# Ethernet-HPS.net
KiCad netlist of a schematic drawn in Altium Designer
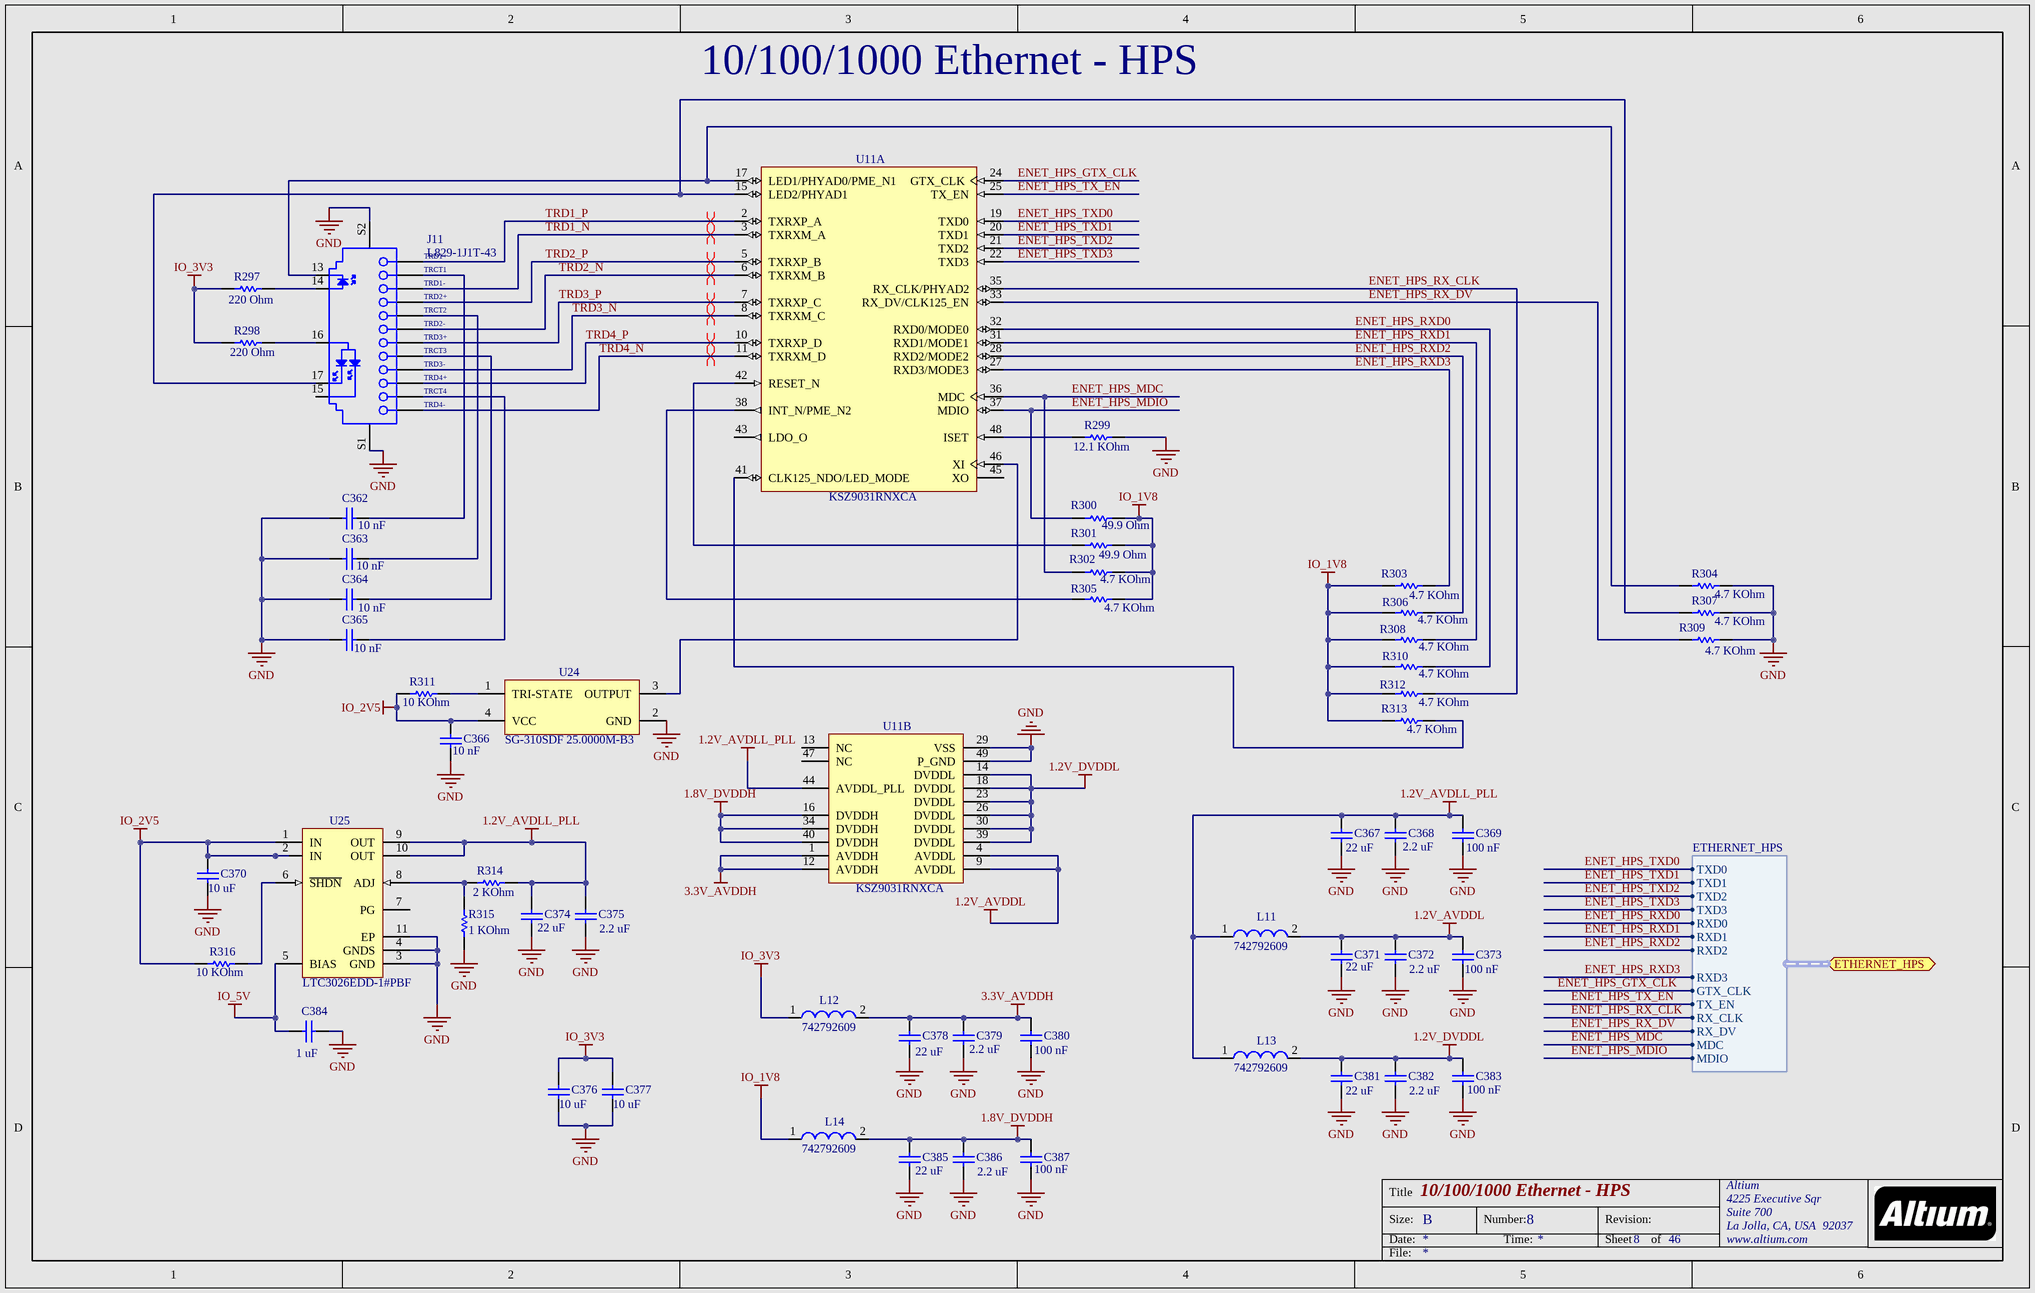
[diagram p0: Ethernet-HPS.SchDoc]

(export (version "E")
  (design (tool "Eeschema 10.0.6"))
  (components
    (comp (ref "C362")
      (value "GRM155R71H103KA88D")
      (footprint "CAPC1005X55X25ML05T10")
      (description "Chip Capacitor, 10 nF, +/- 10%, 50 V, -55 to 125 degC, 0402 (1005 Metric), RoHS, Tape and Reel")
      (fields
        (field (name "TOLERANCE") "10%")
        (field (name "CAPACITANCE") "10 nF")
        (field (name "MANUFACTURER") "Basic Passives")
      )
      (libsource (lib "") (part "CAP-NP-2_1"))
    )
    (comp (ref "C363")
      (value "GRM155R71H103KA88D")
      (footprint "CAPC1005X55X25ML05T10")
      (description "Chip Capacitor, 10 nF, +/- 10%, 50 V, -55 to 125 degC, 0402 (1005 Metric), RoHS, Tape and Reel")
      (fields
        (field (name "TOLERANCE") "10%")
        (field (name "CAPACITANCE") "10 nF")
        (field (name "MANUFACTURER") "Basic Passives")
      )
      (libsource (lib "") (part "CAP-NP-2_1"))
    )
    (comp (ref "C364")
      (value "GRM155R71H103KA88D")
      (footprint "CAPC1005X55X25ML05T10")
      (description "Chip Capacitor, 10 nF, +/- 10%, 50 V, -55 to 125 degC, 0402 (1005 Metric), RoHS, Tape and Reel")
      (fields
        (field (name "TOLERANCE") "10%")
        (field (name "CAPACITANCE") "10 nF")
        (field (name "MANUFACTURER") "Basic Passives")
      )
      (libsource (lib "") (part "CAP-NP-2_1"))
    )
    (comp (ref "C365")
      (value "GRM155R71H103KA88D")
      (footprint "CAPC1005X55X25ML05T10")
      (description "Chip Capacitor, 10 nF, +/- 10%, 50 V, -55 to 125 degC, 0402 (1005 Metric), RoHS, Tape and Reel")
      (fields
        (field (name "TOLERANCE") "10%")
        (field (name "CAPACITANCE") "10 nF")
        (field (name "MANUFACTURER") "Basic Passives")
      )
      (libsource (lib "") (part "CAP-NP-2_1"))
    )
    (comp (ref "C366")
      (value "GRM155R71H103KA88D")
      (footprint "CAPC1005X55X25ML05T10")
      (description "Chip Capacitor, 10 nF, +/- 10%, 50 V, -55 to 125 degC, 0402 (1005 Metric), RoHS, Tape and Reel")
      (fields
        (field (name "TOLERANCE") "10%")
        (field (name "CAPACITANCE") "10 nF")
        (field (name "MANUFACTURER") "Basic Passives")
      )
      (libsource (lib "") (part "CAP-NP-2_1"))
    )
    (comp (ref "C367")
      (value "GRM31CR61E226KE15L")
      (footprint "CAPC3216X180X55ML20T25")
      (description "Chip Capacitor, 22 uF, +/- 10%, 25 V, -55 to 85 degC, 1206 (3216 Metric), RoHS, Tape and Reel")
      (fields (field (name "TOLERANCE") "10%") (field (name "CAPACITANCE") "22 uF"))
      (libsource (lib "") (part "CAP-NP-2_1"))
    )
    (comp (ref "C368")
      (value "GRM188R61A225KE34x")
      (footprint "CAPC1608X90X35ML10T15")
      (description "Chip Capacitor, 2.2 uF, +/- 10%, 10 V, -55 to 85 degC, 0603 (1608 Metric), RoHS, Tape and Reel")
      (fields (field (name "TOLERANCE") "10%") (field (name "CAPACITANCE") "2.2 uF"))
      (libsource (lib "Altium Content Vault") (part "CAP-NP-2"))
    )
    (comp (ref "C369")
      (value "C1005X7R1E104M")
      (footprint "CAPC1005X55X10LL05")
      (description "Chip Capacitor, 0.1 uF, +/- 20%, 25 V, -55 to 125 degC, 0402 (1005 Metric), RoHS, Tape and Reel")
      (fields (field (name "TOLERANCE") "20%") (field (name "CAPACITANCE") "100 nF"))
      (libsource (lib "") (part "CAP-NP-2_1"))
    )
    (comp (ref "C370")
      (value "C2012X5R1C106K085AC")
      (footprint "CAPC2013X100X20NL20")
      (description "Chip Capacitor, 10 uF, +/- 10%, 16 V, -55 to 85 degC, 0805 (2012 Metric), RoHS, Tape and Reel")
      (fields (field (name "TOLERANCE") "10%") (field (name "CAPACITANCE") "10 uF"))
      (libsource (lib "Altium Content Vault") (part "CAP-NP-2"))
    )
    (comp (ref "C371")
      (value "GRM31CR61E226KE15L")
      (footprint "CAPC3216X180X55ML20T25")
      (description "Chip Capacitor, 22 uF, +/- 10%, 25 V, -55 to 85 degC, 1206 (3216 Metric), RoHS, Tape and Reel")
      (fields (field (name "TOLERANCE") "10%") (field (name "CAPACITANCE") "22 uF"))
      (libsource (lib "") (part "CAP-NP-2_1"))
    )
    (comp (ref "C372")
      (value "GRM188R61A225KE34x")
      (footprint "CAPC1608X90X35ML10T15")
      (description "Chip Capacitor, 2.2 uF, +/- 10%, 10 V, -55 to 85 degC, 0603 (1608 Metric), RoHS, Tape and Reel")
      (fields (field (name "TOLERANCE") "10%") (field (name "CAPACITANCE") "2.2 uF"))
      (libsource (lib "Altium Content Vault") (part "CAP-NP-2"))
    )
    (comp (ref "C373")
      (value "C1005X7R1E104M")
      (footprint "CAPC1005X55X10LL05")
      (description "Chip Capacitor, 0.1 uF, +/- 20%, 25 V, -55 to 125 degC, 0402 (1005 Metric), RoHS, Tape and Reel")
      (fields (field (name "TOLERANCE") "20%") (field (name "CAPACITANCE") "100 nF"))
      (libsource (lib "") (part "CAP-NP-2_1"))
    )
    (comp (ref "C374")
      (value "GRM31CR61E226KE15L")
      (footprint "CAPC3216X180X55ML20T25")
      (description "Chip Capacitor, 22 uF, +/- 10%, 25 V, -55 to 85 degC, 1206 (3216 Metric), RoHS, Tape and Reel")
      (fields (field (name "TOLERANCE") "10%") (field (name "CAPACITANCE") "22 uF"))
      (libsource (lib "") (part "CAP-NP-2_1"))
    )
    (comp (ref "C375")
      (value "GRM188R61A225KE34x")
      (footprint "CAPC1608X90X35ML10T15")
      (description "Chip Capacitor, 2.2 uF, +/- 10%, 10 V, -55 to 85 degC, 0603 (1608 Metric), RoHS, Tape and Reel")
      (fields (field (name "TOLERANCE") "10%") (field (name "CAPACITANCE") "2.2 uF"))
      (libsource (lib "Altium Content Vault") (part "CAP-NP-2"))
    )
    (comp (ref "C376")
      (value "C2012X5R1C106K085AC")
      (footprint "CAPC2013X100X20NL20")
      (description "Chip Capacitor, 10 uF, +/- 10%, 16 V, -55 to 85 degC, 0805 (2012 Metric), RoHS, Tape and Reel")
      (fields (field (name "TOLERANCE") "10%") (field (name "CAPACITANCE") "10 uF"))
      (libsource (lib "Altium Content Vault") (part "CAP-NP-2"))
    )
    (comp (ref "C377")
      (value "C2012X5R1C106K085AC")
      (footprint "CAPC2013X100X20NL20")
      (description "Chip Capacitor, 10 uF, +/- 10%, 16 V, -55 to 85 degC, 0805 (2012 Metric), RoHS, Tape and Reel")
      (fields (field (name "TOLERANCE") "10%") (field (name "CAPACITANCE") "10 uF"))
      (libsource (lib "Altium Content Vault") (part "CAP-NP-2"))
    )
    (comp (ref "C378")
      (value "GRM31CR61E226KE15L")
      (footprint "CAPC3216X180X55ML20T25")
      (description "Chip Capacitor, 22 uF, +/- 10%, 25 V, -55 to 85 degC, 1206 (3216 Metric), RoHS, Tape and Reel")
      (fields (field (name "TOLERANCE") "10%") (field (name "CAPACITANCE") "22 uF"))
      (libsource (lib "") (part "CAP-NP-2_1"))
    )
    (comp (ref "C379")
      (value "GRM188R61A225KE34x")
      (footprint "CAPC1608X90X35ML10T15")
      (description "Chip Capacitor, 2.2 uF, +/- 10%, 10 V, -55 to 85 degC, 0603 (1608 Metric), RoHS, Tape and Reel")
      (fields (field (name "TOLERANCE") "10%") (field (name "CAPACITANCE") "2.2 uF"))
      (libsource (lib "Altium Content Vault") (part "CAP-NP-2"))
    )
    (comp (ref "C380")
      (value "C1005X7R1E104M")
      (footprint "CAPC1005X55X10LL05")
      (description "Chip Capacitor, 0.1 uF, +/- 20%, 25 V, -55 to 125 degC, 0402 (1005 Metric), RoHS, Tape and Reel")
      (fields (field (name "TOLERANCE") "20%") (field (name "CAPACITANCE") "100 nF"))
      (libsource (lib "") (part "CAP-NP-2_1"))
    )
    (comp (ref "C381")
      (value "GRM31CR61E226KE15L")
      (footprint "CAPC3216X180X55ML20T25")
      (description "Chip Capacitor, 22 uF, +/- 10%, 25 V, -55 to 85 degC, 1206 (3216 Metric), RoHS, Tape and Reel")
      (fields (field (name "TOLERANCE") "10%") (field (name "CAPACITANCE") "22 uF"))
      (libsource (lib "") (part "CAP-NP-2_1"))
    )
    (comp (ref "C382")
      (value "GRM188R61A225KE34x")
      (footprint "CAPC1608X90X35ML10T15")
      (description "Chip Capacitor, 2.2 uF, +/- 10%, 10 V, -55 to 85 degC, 0603 (1608 Metric), RoHS, Tape and Reel")
      (fields (field (name "TOLERANCE") "10%") (field (name "CAPACITANCE") "2.2 uF"))
      (libsource (lib "Altium Content Vault") (part "CAP-NP-2"))
    )
    (comp (ref "C383")
      (value "C1005X7R1E104M")
      (footprint "CAPC1005X55X10LL05")
      (description "Chip Capacitor, 0.1 uF, +/- 20%, 25 V, -55 to 125 degC, 0402 (1005 Metric), RoHS, Tape and Reel")
      (fields (field (name "TOLERANCE") "20%") (field (name "CAPACITANCE") "100 nF"))
      (libsource (lib "") (part "CAP-NP-2_1"))
    )
    (comp (ref "C384")
      (value "CGB2A1X5R1E105K033BC")
      (footprint "CAPC1005X33X10LL5")
      (description "Chip Capacitor, 1 uF, +/- 10%, 25 V, -55 to 85 degC, 0402 (1005 Metric), RoHS, Tape and Reel")
      (fields (field (name "CAPACITANCE") "1 uF") (field (name "TOLERANCE") "10%"))
      (libsource (lib "Altium Content Vault") (part "CAP-NP-2"))
    )
    (comp (ref "C385")
      (value "GRM31CR61E226KE15L")
      (footprint "CAPC3216X180X55ML20T25")
      (description "Chip Capacitor, 22 uF, +/- 10%, 25 V, -55 to 85 degC, 1206 (3216 Metric), RoHS, Tape and Reel")
      (fields (field (name "TOLERANCE") "10%") (field (name "CAPACITANCE") "22 uF"))
      (libsource (lib "") (part "CAP-NP-2_1"))
    )
    (comp (ref "C386")
      (value "GRM188R61A225KE34x")
      (footprint "CAPC1608X90X35ML10T15")
      (description "Chip Capacitor, 2.2 uF, +/- 10%, 10 V, -55 to 85 degC, 0603 (1608 Metric), RoHS, Tape and Reel")
      (fields (field (name "TOLERANCE") "10%") (field (name "CAPACITANCE") "2.2 uF"))
      (libsource (lib "Altium Content Vault") (part "CAP-NP-2"))
    )
    (comp (ref "C387")
      (value "C1005X7R1E104M")
      (footprint "CAPC1005X55X10LL05")
      (description "Chip Capacitor, 0.1 uF, +/- 20%, 25 V, -55 to 125 degC, 0402 (1005 Metric), RoHS, Tape and Reel")
      (fields (field (name "TOLERANCE") "20%") (field (name "CAPACITANCE") "100 nF"))
      (libsource (lib "") (part "CAP-NP-2_1"))
    )
    (comp (ref "J11")
      (value "L829-1J1T-43")
      (footprint "BELS-L829-1J1T-43_V")
      (description "Gigabit MagJack(R) Ultra Low Profile, 10/100/1000 Base-T, 19-Pin THD, RoHS, Tray")
      (libsource (lib "Altium Content Vault") (part "RJ45-17-2SHLD"))
    )
    (comp (ref "L11")
      (value "742792609")
      (footprint "SMD-0603")
      (description "SMD EMI Suppression Ferrite Bead WE-CBF, Z = 30 Ohm")
      (libsource (lib "Altium Content Vault") (part "CMP-0220-00193-1"))
    )
    (comp (ref "L12")
      (value "742792609")
      (footprint "SMD-0603")
      (description "SMD EMI Suppression Ferrite Bead WE-CBF, Z = 30 Ohm")
      (libsource (lib "Altium Content Vault") (part "CMP-0220-00193-1"))
    )
    (comp (ref "L13")
      (value "742792609")
      (footprint "SMD-0603")
      (description "SMD EMI Suppression Ferrite Bead WE-CBF, Z = 30 Ohm")
      (libsource (lib "Altium Content Vault") (part "CMP-0220-00193-1"))
    )
    (comp (ref "L14")
      (value "742792609")
      (footprint "SMD-0603")
      (description "SMD EMI Suppression Ferrite Bead WE-CBF, Z = 30 Ohm")
      (libsource (lib "Altium Content Vault") (part "CMP-0220-00193-1"))
    )
    (comp (ref "R297")
      (value "ERJ-2GEJ221X")
      (footprint "RESC1005X40X25LL05T05")
      (description "Chip Resistor, 220 Ohm, +/- 5%, 100 mW, -55 to 155 degC, 0402 (1005 Metric), RoHS, Tape and Reel")
      (fields
        (field (name "RESISTANCE") "220 Ohm")
        (field (name "TOLERANCE") "5%")
        (field (name "MANUFACTURER") "Basic Passives")
      )
      (libsource (lib "Altium Content Vault") (part "RES-2"))
    )
    (comp (ref "R298")
      (value "ERJ-2GEJ221X")
      (footprint "RESC1005X40X25LL05T05")
      (description "Chip Resistor, 220 Ohm, +/- 5%, 100 mW, -55 to 155 degC, 0402 (1005 Metric), RoHS, Tape and Reel")
      (fields
        (field (name "RESISTANCE") "220 Ohm")
        (field (name "TOLERANCE") "5%")
        (field (name "MANUFACTURER") "Basic Passives")
      )
      (libsource (lib "Altium Content Vault") (part "RES-2"))
    )
    (comp (ref "R299")
      (value "CRCW040212K1FKED")
      (footprint "RESC1005X40X25LL05T05")
      (description "Chip Resistor, 12.1 KOhm, +/- 1%, 63 mW, -55 to 155 degC, 0402 (1005 Metric), RoHS, Tape and Reel")
      (fields
        (field (name "RESISTANCE") "12.1 KOhm")
        (field (name "TOLERANCE") "1%")
        (field (name "MANUFACTURER") "Basic Passives")
      )
      (libsource (lib "Altium Content Vault") (part "RES-2"))
    )
    (comp (ref "R300")
      (value "NRC04F49R9TRF")
      (footprint "RESC1005X35X25NL8T10")
      (description "Chip Resistor, 49.9 Ohm, +/- 1%, 0.06 W, -55 to 155 degC, 0402 (1005 Metric), RoHS, Tape and Reel")
      (fields (field (name "TOLERANCE") "1%") (field (name "RESISTANCE") "49.9 Ohm"))
      (libsource (lib "Altium Content Vault") (part "RES-2"))
    )
    (comp (ref "R301")
      (value "NRC04F49R9TRF")
      (footprint "RESC1005X35X25NL8T10")
      (description "Chip Resistor, 49.9 Ohm, +/- 1%, 0.06 W, -55 to 155 degC, 0402 (1005 Metric), RoHS, Tape and Reel")
      (fields (field (name "TOLERANCE") "1%") (field (name "RESISTANCE") "49.9 Ohm"))
      (libsource (lib "Altium Content Vault") (part "RES-2"))
    )
    (comp (ref "R302")
      (value "ERJ-2RKF4701X")
      (footprint "RESC1005X40X25LL05T05")
      (description "Chip Resistor, 4.7 KOhm, +/- 1%, 0.1 W, -55 to 155 degC, 0402 (1005 Metric), RoHS, Tape and Reel")
      (fields (field (name "TOLERANCE") "1%") (field (name "RESISTANCE") "4.7 KOhm"))
      (libsource (lib "Altium Content Vault") (part "RES-2"))
    )
    (comp (ref "R303")
      (value "ERJ-2RKF4701X")
      (footprint "RESC1005X40X25LL05T05")
      (description "Chip Resistor, 4.7 KOhm, +/- 1%, 0.1 W, -55 to 155 degC, 0402 (1005 Metric), RoHS, Tape and Reel")
      (fields (field (name "TOLERANCE") "1%") (field (name "RESISTANCE") "4.7 KOhm"))
      (libsource (lib "Altium Content Vault") (part "RES-2"))
    )
    (comp (ref "R304")
      (value "ERJ-2RKF4701X")
      (footprint "RESC1005X40X25LL05T05")
      (description "Chip Resistor, 4.7 KOhm, +/- 1%, 0.1 W, -55 to 155 degC, 0402 (1005 Metric), RoHS, Tape and Reel")
      (fields (field (name "TOLERANCE") "1%") (field (name "RESISTANCE") "4.7 KOhm"))
      (libsource (lib "Altium Content Vault") (part "RES-2"))
    )
    (comp (ref "R305")
      (value "ERJ-2RKF4701X")
      (footprint "RESC1005X40X25LL05T05")
      (description "Chip Resistor, 4.7 KOhm, +/- 1%, 0.1 W, -55 to 155 degC, 0402 (1005 Metric), RoHS, Tape and Reel")
      (fields (field (name "TOLERANCE") "1%") (field (name "RESISTANCE") "4.7 KOhm"))
      (libsource (lib "Altium Content Vault") (part "RES-2"))
    )
    (comp (ref "R306")
      (value "ERJ-2RKF4701X")
      (footprint "RESC1005X40X25LL05T05")
      (description "Chip Resistor, 4.7 KOhm, +/- 1%, 0.1 W, -55 to 155 degC, 0402 (1005 Metric), RoHS, Tape and Reel")
      (fields (field (name "TOLERANCE") "1%") (field (name "RESISTANCE") "4.7 KOhm"))
      (libsource (lib "Altium Content Vault") (part "RES-2"))
    )
    (comp (ref "R307")
      (value "ERJ-2RKF4701X")
      (footprint "RESC1005X40X25LL05T05")
      (description "Chip Resistor, 4.7 KOhm, +/- 1%, 0.1 W, -55 to 155 degC, 0402 (1005 Metric), RoHS, Tape and Reel")
      (fields (field (name "TOLERANCE") "1%") (field (name "RESISTANCE") "4.7 KOhm"))
      (libsource (lib "Altium Content Vault") (part "RES-2"))
    )
    (comp (ref "R308")
      (value "ERJ-2RKF4701X")
      (footprint "RESC1005X40X25LL05T05")
      (description "Chip Resistor, 4.7 KOhm, +/- 1%, 0.1 W, -55 to 155 degC, 0402 (1005 Metric), RoHS, Tape and Reel")
      (fields (field (name "TOLERANCE") "1%") (field (name "RESISTANCE") "4.7 KOhm"))
      (libsource (lib "Altium Content Vault") (part "RES-2"))
    )
    (comp (ref "R309")
      (value "ERJ-2RKF4701X")
      (footprint "RESC1005X40X25LL05T05")
      (description "Chip Resistor, 4.7 KOhm, +/- 1%, 0.1 W, -55 to 155 degC, 0402 (1005 Metric), RoHS, Tape and Reel")
      (fields (field (name "TOLERANCE") "1%") (field (name "RESISTANCE") "4.7 KOhm"))
      (libsource (lib "Altium Content Vault") (part "RES-2"))
    )
    (comp (ref "R310")
      (value "ERJ-2RKF4701X")
      (footprint "RESC1005X40X25LL05T05")
      (description "Chip Resistor, 4.7 KOhm, +/- 1%, 0.1 W, -55 to 155 degC, 0402 (1005 Metric), RoHS, Tape and Reel")
      (fields (field (name "TOLERANCE") "1%") (field (name "RESISTANCE") "4.7 KOhm"))
      (libsource (lib "Altium Content Vault") (part "RES-2"))
    )
    (comp (ref "R311")
      (value "ERJ-2RKF1002X")
      (footprint "RESC1005X40X25NL05T05")
      (description "Chip Resistor, 10 KOhm, +/- 1%, 100 mW, -55 to 155 degC, 0402 (1005 Metric), RoHS, Tape and Reel")
      (fields
        (field (name "TOLERANCE") "1%")
        (field (name "RESISTANCE") "10 KOhm")
        (field (name "MANUFACTURER") "Basic Passives")
      )
      (libsource (lib "Altium Content Vault") (part "RES-2"))
    )
    (comp (ref "R312")
      (value "ERJ-2RKF4701X")
      (footprint "RESC1005X40X25LL05T05")
      (description "Chip Resistor, 4.7 KOhm, +/- 1%, 0.1 W, -55 to 155 degC, 0402 (1005 Metric), RoHS, Tape and Reel")
      (fields (field (name "TOLERANCE") "1%") (field (name "RESISTANCE") "4.7 KOhm"))
      (libsource (lib "Altium Content Vault") (part "RES-2"))
    )
    (comp (ref "R313")
      (value "ERJ-2RKF4701X")
      (footprint "RESC1005X40X25LL05T05")
      (description "Chip Resistor, 4.7 KOhm, +/- 1%, 0.1 W, -55 to 155 degC, 0402 (1005 Metric), RoHS, Tape and Reel")
      (fields (field (name "TOLERANCE") "1%") (field (name "RESISTANCE") "4.7 KOhm"))
      (libsource (lib "Altium Content Vault") (part "RES-2"))
    )
    (comp (ref "R314")
      (value "ERJ-2RKF2001X")
      (footprint "RESC1005X40X25NL05T05")
      (description "Chip Resistor, 2 KOhm, +/- 1%, 100 mW, -55 to 155 degC, 0402 (1005 Metric), RoHS, Tape and Reel")
      (fields
        (field (name "TOLERANCE") "1%")
        (field (name "RESISTANCE") "2 KOhm")
        (field (name "MANUFACTURER") "Basic Passives")
      )
      (libsource (lib "Altium Content Vault") (part "RES-2"))
    )
    (comp (ref "R315")
      (value "ERJ-2RKF1001X")
      (footprint "RESC1005X40X25LL05T05")
      (description "Chip Resistor, 1 KOhm, +/- 1%, 100 mW, -55 to 155 degC, 0402 (1005 Metric), RoHS, Tape and Reel")
      (fields
        (field (name "RESISTANCE") "1 KOhm")
        (field (name "TOLERANCE") "1%")
        (field (name "MANUFACTURER") "Basic Passives")
      )
      (libsource (lib "Altium Content Vault") (part "RES-2"))
    )
    (comp (ref "R316")
      (value "ERJ-2RKF1002X")
      (footprint "RESC1005X40X25NL05T05")
      (description "Chip Resistor, 10 KOhm, +/- 1%, 100 mW, -55 to 155 degC, 0402 (1005 Metric), RoHS, Tape and Reel")
      (fields
        (field (name "TOLERANCE") "1%")
        (field (name "RESISTANCE") "10 KOhm")
        (field (name "MANUFACTURER") "Basic Passives")
      )
      (libsource (lib "Altium Content Vault") (part "RES-2"))
    )
    (comp (ref "U11")
      (value "KSZ9031RNXCA")
      (footprint "MICL-QFN-48_V")
      (description "Gigabit Ethernet Transceiver with RGMII Support, 1.14 to 1.26 V, 0 to 70 degC, 48-Pin QFN, RoHS")
      (fields (field (name "MANUFACTURER") "Micrel"))
      (libsource (lib "") (part "MICL-KSZ9031RNX-48_1"))
    )
    (comp (ref "U24")
      (value "SG-310SDF 25.0000M-B3")
      (footprint "EPSON-SG-310-4_V")
      (description "Crystal Oscillator (SPXO), 2.5 V, 25 MHz, -20 to 70 degC, 4-Pin SMD, RoHS, Tape and Reel")
      (libsource (lib "Altium Content Vault") (part "XTAL-1-3-4_B"))
    )
    (comp (ref "U25")
      (value "LTC3026EDD-1#PBF")
      (footprint "LT-DD-10_V")
      (fields (field (name "MANUFACTURER") "Linear Technology"))
      (libsource (lib "Altium Content Vault") (part "LT-LTC3026-1-10"))
    )
  )
  (nets
    (net (code "2") (name "/ENET_HPS_GTX_CLK") (class "Default")
      (node (ref "U11") (pin "24") (pinfunction "GTX_CLK_24") (pintype "input"))
    )
    (net (code "3") (name "/ENET_HPS_MDC") (class "Default")
      (node (ref "R302") (pin "1") (pinfunction "1_1") (pintype "passive"))
      (node (ref "U11") (pin "36") (pinfunction "MDC_36") (pintype "input"))
    )
    (net (code "4") (name "/ENET_HPS_MDIO") (class "Default")
      (node (ref "R300") (pin "1") (pinfunction "1_1") (pintype "passive"))
      (node (ref "U11") (pin "37") (pinfunction "MDIO_37") (pintype "bidirectional"))
    )
    (net (code "5") (name "/ENET_HPS_RXD0") (class "Default")
      (node (ref "R310") (pin "2") (pinfunction "2_2") (pintype "passive"))
      (node (ref "U11") (pin "32") (pinfunction "RXD0/MODE0_32") (pintype "bidirectional"))
    )
    (net (code "6") (name "/ENET_HPS_RXD1") (class "Default")
      (node (ref "R308") (pin "2") (pinfunction "2_2") (pintype "passive"))
      (node (ref "U11") (pin "31") (pinfunction "RXD1/MODE1_31") (pintype "bidirectional"))
    )
    (net (code "7") (name "/ENET_HPS_RXD2") (class "Default")
      (node (ref "R306") (pin "2") (pinfunction "2_2") (pintype "passive"))
      (node (ref "U11") (pin "28") (pinfunction "RXD2/MODE2_28") (pintype "bidirectional"))
    )
    (net (code "8") (name "/ENET_HPS_RXD3") (class "Default")
      (node (ref "R303") (pin "2") (pinfunction "2_2") (pintype "passive"))
      (node (ref "U11") (pin "27") (pinfunction "RXD3/MODE3_27") (pintype "bidirectional"))
    )
    (net (code "9") (name "/ENET_HPS_RX_CLK") (class "Default")
      (node (ref "R312") (pin "2") (pinfunction "2_2") (pintype "passive"))
      (node (ref "U11") (pin "35") (pinfunction "RX_CLK/PHYAD2_35") (pintype "bidirectional"))
    )
    (net (code "10") (name "/ENET_HPS_RX_DV") (class "Default")
      (node (ref "R309") (pin "1") (pinfunction "1_1") (pintype "passive"))
      (node (ref "U11") (pin "33") (pinfunction "RX_DV/CLK125_EN_33") (pintype "bidirectional"))
    )
    (net (code "11") (name "/ENET_HPS_TXD0") (class "Default")
      (node (ref "U11") (pin "19") (pinfunction "TXD0_19") (pintype "input"))
    )
    (net (code "12") (name "/ENET_HPS_TXD1") (class "Default")
      (node (ref "U11") (pin "20") (pinfunction "TXD1_20") (pintype "input"))
    )
    (net (code "13") (name "/ENET_HPS_TXD2") (class "Default")
      (node (ref "U11") (pin "21") (pinfunction "TXD2_21") (pintype "input"))
    )
    (net (code "14") (name "/ENET_HPS_TXD3") (class "Default")
      (node (ref "U11") (pin "22") (pinfunction "TXD3_22") (pintype "input"))
    )
    (net (code "15") (name "/ENET_HPS_TX_EN") (class "Default")
      (node (ref "U11") (pin "25") (pinfunction "TX_EN_25") (pintype "input"))
    )
    (net (code "16") (name "/TRD1_N") (class "Default")
      (node (ref "J11") (pin "3") (pinfunction "TRD1-_3") (pintype "passive"))
      (node (ref "U11") (pin "3") (pinfunction "TXRXM_A_3") (pintype "bidirectional"))
    )
    (net (code "17") (name "/TRD1_P") (class "Default")
      (node (ref "J11") (pin "1") (pinfunction "TRD1+_1") (pintype "passive"))
      (node (ref "U11") (pin "2") (pinfunction "TXRXP_A_2") (pintype "bidirectional"))
    )
    (net (code "18") (name "/TRD2_N") (class "Default")
      (node (ref "J11") (pin "6") (pinfunction "TRD2-_6") (pintype "passive"))
      (node (ref "U11") (pin "6") (pinfunction "TXRXM_B_6") (pintype "bidirectional"))
    )
    (net (code "19") (name "/TRD2_P") (class "Default")
      (node (ref "J11") (pin "4") (pinfunction "TRD2+_4") (pintype "passive"))
      (node (ref "U11") (pin "5") (pinfunction "TXRXP_B_5") (pintype "bidirectional"))
    )
    (net (code "20") (name "/TRD3_N") (class "Default")
      (node (ref "J11") (pin "9") (pinfunction "TRD3-_9") (pintype "passive"))
      (node (ref "U11") (pin "8") (pinfunction "TXRXM_C_8") (pintype "bidirectional"))
    )
    (net (code "21") (name "/TRD3_P") (class "Default")
      (node (ref "J11") (pin "7") (pinfunction "TRD3+_7") (pintype "passive"))
      (node (ref "U11") (pin "7") (pinfunction "TXRXP_C_7") (pintype "bidirectional"))
    )
    (net (code "22") (name "/TRD4_N") (class "Default")
      (node (ref "J11") (pin "12") (pinfunction "TRD4-_12") (pintype "passive"))
      (node (ref "U11") (pin "11") (pinfunction "TXRXM_D_11") (pintype "bidirectional"))
    )
    (net (code "23") (name "/TRD4_P") (class "Default")
      (node (ref "J11") (pin "10") (pinfunction "TRD4+_10") (pintype "passive"))
      (node (ref "U11") (pin "10") (pinfunction "TXRXP_D_10") (pintype "bidirectional"))
    )
    (net (code "25") (name "1.2V_AVDDL") (class "Default")
      (node (ref "C371") (pin "2") (pinfunction "2_2") (pintype "passive"))
      (node (ref "C372") (pin "2") (pinfunction "2_2") (pintype "passive"))
      (node (ref "C373") (pin "2") (pinfunction "2_2") (pintype "passive"))
      (node (ref "L11") (pin "2") (pinfunction "2_2") (pintype "passive"))
      (node (ref "U11") (pin "4") (pinfunction "AVDDL_4") (pintype "power_in"))
      (node (ref "U11") (pin "9") (pinfunction "AVDDL_9") (pintype "power_in"))
    )
    (net (code "26") (name "1.2V_AVDLL_PLL") (class "Default")
      (node (ref "C367") (pin "2") (pinfunction "2_2") (pintype "passive"))
      (node (ref "C368") (pin "2") (pinfunction "2_2") (pintype "passive"))
      (node (ref "C369") (pin "2") (pinfunction "2_2") (pintype "passive"))
      (node (ref "C374") (pin "2") (pinfunction "2_2") (pintype "passive"))
      (node (ref "C375") (pin "2") (pinfunction "2_2") (pintype "passive"))
      (node (ref "L11") (pin "1") (pinfunction "1_1") (pintype "passive"))
      (node (ref "L13") (pin "1") (pinfunction "1_1") (pintype "passive"))
      (node (ref "R314") (pin "2") (pinfunction "2_2") (pintype "passive"))
      (node (ref "U11") (pin "44") (pinfunction "AVDDL_PLL_44") (pintype "power_in"))
      (node (ref "U25") (pin "10") (pinfunction "OUT_10") (pintype "power_in"))
      (node (ref "U25") (pin "9") (pinfunction "OUT_9") (pintype "power_in"))
    )
    (net (code "27") (name "1.2V_DVDDL") (class "Default")
      (node (ref "C381") (pin "2") (pinfunction "2_2") (pintype "passive"))
      (node (ref "C382") (pin "2") (pinfunction "2_2") (pintype "passive"))
      (node (ref "C383") (pin "2") (pinfunction "2_2") (pintype "passive"))
      (node (ref "L13") (pin "2") (pinfunction "2_2") (pintype "passive"))
      (node (ref "U11") (pin "14") (pinfunction "DVDDL_14") (pintype "power_in"))
      (node (ref "U11") (pin "18") (pinfunction "DVDDL_18") (pintype "power_in"))
      (node (ref "U11") (pin "23") (pinfunction "DVDDL_23") (pintype "power_in"))
      (node (ref "U11") (pin "26") (pinfunction "DVDDL_26") (pintype "power_in"))
      (node (ref "U11") (pin "30") (pinfunction "DVDDL_30") (pintype "power_in"))
      (node (ref "U11") (pin "39") (pinfunction "DVDDL_39") (pintype "power_in"))
    )
    (net (code "28") (name "1.8V_DVDDH") (class "Default")
      (node (ref "C385") (pin "2") (pinfunction "2_2") (pintype "passive"))
      (node (ref "C386") (pin "2") (pinfunction "2_2") (pintype "passive"))
      (node (ref "C387") (pin "1") (pinfunction "1_1") (pintype "passive"))
      (node (ref "L14") (pin "2") (pinfunction "2_2") (pintype "passive"))
      (node (ref "U11") (pin "16") (pinfunction "DVDDH_16") (pintype "power_in"))
      (node (ref "U11") (pin "34") (pinfunction "DVDDH_34") (pintype "power_in"))
      (node (ref "U11") (pin "40") (pinfunction "DVDDH_40") (pintype "power_in"))
    )
    (net (code "29") (name "3.3V_AVDDH") (class "Default")
      (node (ref "C378") (pin "2") (pinfunction "2_2") (pintype "passive"))
      (node (ref "C379") (pin "2") (pinfunction "2_2") (pintype "passive"))
      (node (ref "C380") (pin "2") (pinfunction "2_2") (pintype "passive"))
      (node (ref "L12") (pin "2") (pinfunction "2_2") (pintype "passive"))
      (node (ref "U11") (pin "1") (pinfunction "AVDDH_1") (pintype "power_in"))
      (node (ref "U11") (pin "12") (pinfunction "AVDDH_12") (pintype "power_in"))
    )
    (net (code "30") (name "GND") (class "Default")
      (node (ref "C362") (pin "1") (pinfunction "1_1") (pintype "passive"))
      (node (ref "C363") (pin "1") (pinfunction "1_1") (pintype "passive"))
      (node (ref "C364") (pin "1") (pinfunction "1_1") (pintype "passive"))
      (node (ref "C365") (pin "1") (pinfunction "1_1") (pintype "passive"))
      (node (ref "C366") (pin "1") (pinfunction "1_1") (pintype "passive"))
      (node (ref "C367") (pin "1") (pinfunction "1_1") (pintype "passive"))
      (node (ref "C368") (pin "1") (pinfunction "1_1") (pintype "passive"))
      (node (ref "C369") (pin "1") (pinfunction "1_1") (pintype "passive"))
      (node (ref "C370") (pin "1") (pinfunction "1_1") (pintype "passive"))
      (node (ref "C371") (pin "1") (pinfunction "1_1") (pintype "passive"))
      (node (ref "C372") (pin "1") (pinfunction "1_1") (pintype "passive"))
      (node (ref "C373") (pin "1") (pinfunction "1_1") (pintype "passive"))
      (node (ref "C374") (pin "1") (pinfunction "1_1") (pintype "passive"))
      (node (ref "C375") (pin "1") (pinfunction "1_1") (pintype "passive"))
      (node (ref "C376") (pin "1") (pinfunction "1_1") (pintype "passive"))
      (node (ref "C377") (pin "1") (pinfunction "1_1") (pintype "passive"))
      (node (ref "C378") (pin "1") (pinfunction "1_1") (pintype "passive"))
      (node (ref "C379") (pin "1") (pinfunction "1_1") (pintype "passive"))
      (node (ref "C380") (pin "1") (pinfunction "1_1") (pintype "passive"))
      (node (ref "C381") (pin "1") (pinfunction "1_1") (pintype "passive"))
      (node (ref "C382") (pin "1") (pinfunction "1_1") (pintype "passive"))
      (node (ref "C383") (pin "1") (pinfunction "1_1") (pintype "passive"))
      (node (ref "C384") (pin "1") (pinfunction "1_1") (pintype "passive"))
      (node (ref "C385") (pin "1") (pinfunction "1_1") (pintype "passive"))
      (node (ref "C386") (pin "1") (pinfunction "1_1") (pintype "passive"))
      (node (ref "C387") (pin "2") (pinfunction "2_2") (pintype "passive"))
      (node (ref "J11") (pin "S1") (pinfunction "S1_S1") (pintype "passive"))
      (node (ref "J11") (pin "S2") (pinfunction "S2_S2") (pintype "passive"))
      (node (ref "R299") (pin "2") (pinfunction "2_2") (pintype "passive"))
      (node (ref "R304") (pin "2") (pinfunction "2_2") (pintype "passive"))
      (node (ref "R307") (pin "2") (pinfunction "2_2") (pintype "passive"))
      (node (ref "R309") (pin "2") (pinfunction "2_2") (pintype "passive"))
      (node (ref "R315") (pin "1") (pinfunction "1_1") (pintype "passive"))
      (node (ref "U11") (pin "29") (pinfunction "VSS_29") (pintype "power_in"))
      (node (ref "U11") (pin "49") (pinfunction "P_GND_49") (pintype "power_in"))
      (node (ref "U24") (pin "2") (pinfunction "GND_2") (pintype "power_in"))
      (node (ref "U25") (pin "11") (pinfunction "EP_11") (pintype "power_in"))
      (node (ref "U25") (pin "3") (pinfunction "GND_3") (pintype "power_in"))
      (node (ref "U25") (pin "4") (pinfunction "GNDS_4") (pintype "power_in"))
    )
    (net (code "31") (name "IO_1V8") (class "Default")
      (node (ref "L14") (pin "1") (pinfunction "1_1") (pintype "passive"))
      (node (ref "R300") (pin "2") (pinfunction "2_2") (pintype "passive"))
      (node (ref "R301") (pin "2") (pinfunction "2_2") (pintype "passive"))
      (node (ref "R302") (pin "2") (pinfunction "2_2") (pintype "passive"))
      (node (ref "R303") (pin "1") (pinfunction "1_1") (pintype "passive"))
      (node (ref "R305") (pin "2") (pinfunction "2_2") (pintype "passive"))
      (node (ref "R306") (pin "1") (pinfunction "1_1") (pintype "passive"))
      (node (ref "R308") (pin "1") (pinfunction "1_1") (pintype "passive"))
      (node (ref "R310") (pin "1") (pinfunction "1_1") (pintype "passive"))
      (node (ref "R312") (pin "1") (pinfunction "1_1") (pintype "passive"))
      (node (ref "R313") (pin "1") (pinfunction "1_1") (pintype "passive"))
    )
    (net (code "32") (name "IO_2V5") (class "Default")
      (node (ref "C366") (pin "2") (pinfunction "2_2") (pintype "passive"))
      (node (ref "C370") (pin "2") (pinfunction "2_2") (pintype "passive"))
      (node (ref "R311") (pin "1") (pinfunction "1_1") (pintype "passive"))
      (node (ref "R316") (pin "1") (pinfunction "1_1") (pintype "passive"))
      (node (ref "U24") (pin "4") (pinfunction "VCC_4") (pintype "power_in"))
      (node (ref "U25") (pin "1") (pinfunction "IN_1") (pintype "power_in"))
      (node (ref "U25") (pin "2") (pinfunction "IN_2") (pintype "power_in"))
    )
    (net (code "33") (name "IO_3V3") (class "Default")
      (node (ref "C376") (pin "2") (pinfunction "2_2") (pintype "passive"))
      (node (ref "C377") (pin "2") (pinfunction "2_2") (pintype "passive"))
      (node (ref "L12") (pin "1") (pinfunction "1_1") (pintype "passive"))
      (node (ref "R297") (pin "1") (pinfunction "1_1") (pintype "passive"))
      (node (ref "R298") (pin "1") (pinfunction "1_1") (pintype "passive"))
    )
    (net (code "34") (name "IO_5V") (class "Default")
      (node (ref "C384") (pin "2") (pinfunction "2_2") (pintype "passive"))
      (node (ref "U25") (pin "5") (pinfunction "BIAS_5") (pintype "power_in"))
    )
    (net (code "35") (name "Net-(J11-Pad14)") (class "Default")
      (node (ref "J11") (pin "14") (pinfunction "14_14") (pintype "passive"))
      (node (ref "R297") (pin "2") (pinfunction "2_2") (pintype "passive"))
    )
    (net (code "36") (name "Net-(J11-Pad16)") (class "Default")
      (node (ref "J11") (pin "16") (pinfunction "16_16") (pintype "passive"))
      (node (ref "R298") (pin "2") (pinfunction "2_2") (pintype "passive"))
    )
    (net (code "37") (name "Net-(J11-TRCT1)") (class "Default")
      (node (ref "C362") (pin "2") (pinfunction "2_2") (pintype "passive"))
      (node (ref "J11") (pin "2") (pinfunction "TRCT1_2") (pintype "passive"))
    )
    (net (code "38") (name "Net-(J11-TRCT2)") (class "Default")
      (node (ref "C363") (pin "2") (pinfunction "2_2") (pintype "passive"))
      (node (ref "J11") (pin "5") (pinfunction "TRCT2_5") (pintype "passive"))
    )
    (net (code "39") (name "Net-(J11-TRCT3)") (class "Default")
      (node (ref "C364") (pin "2") (pinfunction "2_2") (pintype "passive"))
      (node (ref "J11") (pin "8") (pinfunction "TRCT3_8") (pintype "passive"))
    )
    (net (code "40") (name "Net-(J11-TRCT4)") (class "Default")
      (node (ref "C365") (pin "2") (pinfunction "2_2") (pintype "passive"))
      (node (ref "J11") (pin "11") (pinfunction "TRCT4_11") (pintype "passive"))
    )
    (net (code "41") (name "Net-(U11A-CLK125_NDO{slash}LED_MODE)") (class "Default")
      (node (ref "R313") (pin "2") (pinfunction "2_2") (pintype "passive"))
      (node (ref "U11") (pin "41") (pinfunction "CLK125_NDO/LED_MODE_41") (pintype "bidirectional"))
    )
    (net (code "42") (name "Net-(U11A-INT_N{slash}PME_N2)") (class "Default")
      (node (ref "R305") (pin "1") (pinfunction "1_1") (pintype "passive"))
      (node (ref "U11") (pin "38") (pinfunction "INT_N/PME_N2_38") (pintype "output"))
    )
    (net (code "43") (name "Net-(U11A-ISET)") (class "Default")
      (node (ref "R299") (pin "1") (pinfunction "1_1") (pintype "passive"))
      (node (ref "U11") (pin "48") (pinfunction "ISET_48") (pintype "input"))
    )
    (net (code "44") (name "Net-(U11A-LED1{slash}PHYAD0{slash}PME_N1)") (class "Default")
      (node (ref "J11") (pin "13") (pinfunction "13_13") (pintype "passive"))
      (node (ref "R304") (pin "1") (pinfunction "1_1") (pintype "passive"))
      (node (ref "U11") (pin "17") (pinfunction "LED1/PHYAD0/PME_N1_17") (pintype "bidirectional"))
    )
    (net (code "45") (name "Net-(U11A-LED2{slash}PHYAD1)") (class "Default")
      (node (ref "J11") (pin "17") (pinfunction "17_17") (pintype "passive"))
      (node (ref "R307") (pin "1") (pinfunction "1_1") (pintype "passive"))
      (node (ref "U11") (pin "15") (pinfunction "LED2/PHYAD1_15") (pintype "bidirectional"))
    )
    (net (code "46") (name "Net-(U11A-RESET_N)") (class "Default")
      (node (ref "R301") (pin "1") (pinfunction "1_1") (pintype "passive"))
      (node (ref "U11") (pin "42") (pinfunction "RESET_N_42") (pintype "input"))
    )
    (net (code "47") (name "Net-(U11A-XI)") (class "Default")
      (node (ref "U11") (pin "46") (pinfunction "XI_46") (pintype "input"))
      (node (ref "U24") (pin "3") (pinfunction "OUTPUT_3") (pintype "passive"))
    )
    (net (code "48") (name "Net-(U24-TRI-STATE)") (class "Default")
      (node (ref "R311") (pin "2") (pinfunction "2_2") (pintype "passive"))
      (node (ref "U24") (pin "1") (pinfunction "TRI-STATE_1") (pintype "passive"))
    )
    (net (code "49") (name "Net-(U25-ADJ)") (class "Default")
      (node (ref "R314") (pin "1") (pinfunction "1_1") (pintype "passive"))
      (node (ref "R315") (pin "2") (pinfunction "2_2") (pintype "passive"))
      (node (ref "U25") (pin "8") (pinfunction "ADJ_8") (pintype "input"))
    )
    (net (code "50") (name "Net-(U25-~{SHDN})") (class "Default")
      (node (ref "R316") (pin "2") (pinfunction "2_2") (pintype "passive"))
      (node (ref "U25") (pin "6") (pinfunction "~{SHDN}_6") (pintype "input"))
    )
    (net (code "51") (name "unconnected-(J11-Pad15)") (class "Default")
      (node (ref "J11") (pin "15") (pinfunction "15_15") (pintype "passive"))
    )
    (net (code "52") (name "unconnected-(U11A-LDO_O-Pad43)") (class "Default")
      (node (ref "U11") (pin "43") (pinfunction "LDO_O_43") (pintype "output"))
    )
    (net (code "53") (name "unconnected-(U11A-XO-Pad45)") (class "Default")
      (node (ref "U11") (pin "45") (pinfunction "XO_45") (pintype "passive"))
    )
    (net (code "54") (name "unconnected-(U11B-NC-Pad13)") (class "Default")
      (node (ref "U11") (pin "13") (pinfunction "NC_13") (pintype "passive"))
    )
    (net (code "55") (name "unconnected-(U11B-NC-Pad47)") (class "Default")
      (node (ref "U11") (pin "47") (pinfunction "NC_47") (pintype "passive"))
    )
    (net (code "56") (name "unconnected-(U25-PG-Pad7)") (class "Default")
      (node (ref "U25") (pin "7") (pinfunction "PG_7") (pintype "tri_state"))
    )
  )
)
